# FLASH.net
KiCad netlist of a schematic drawn in Altium Designer
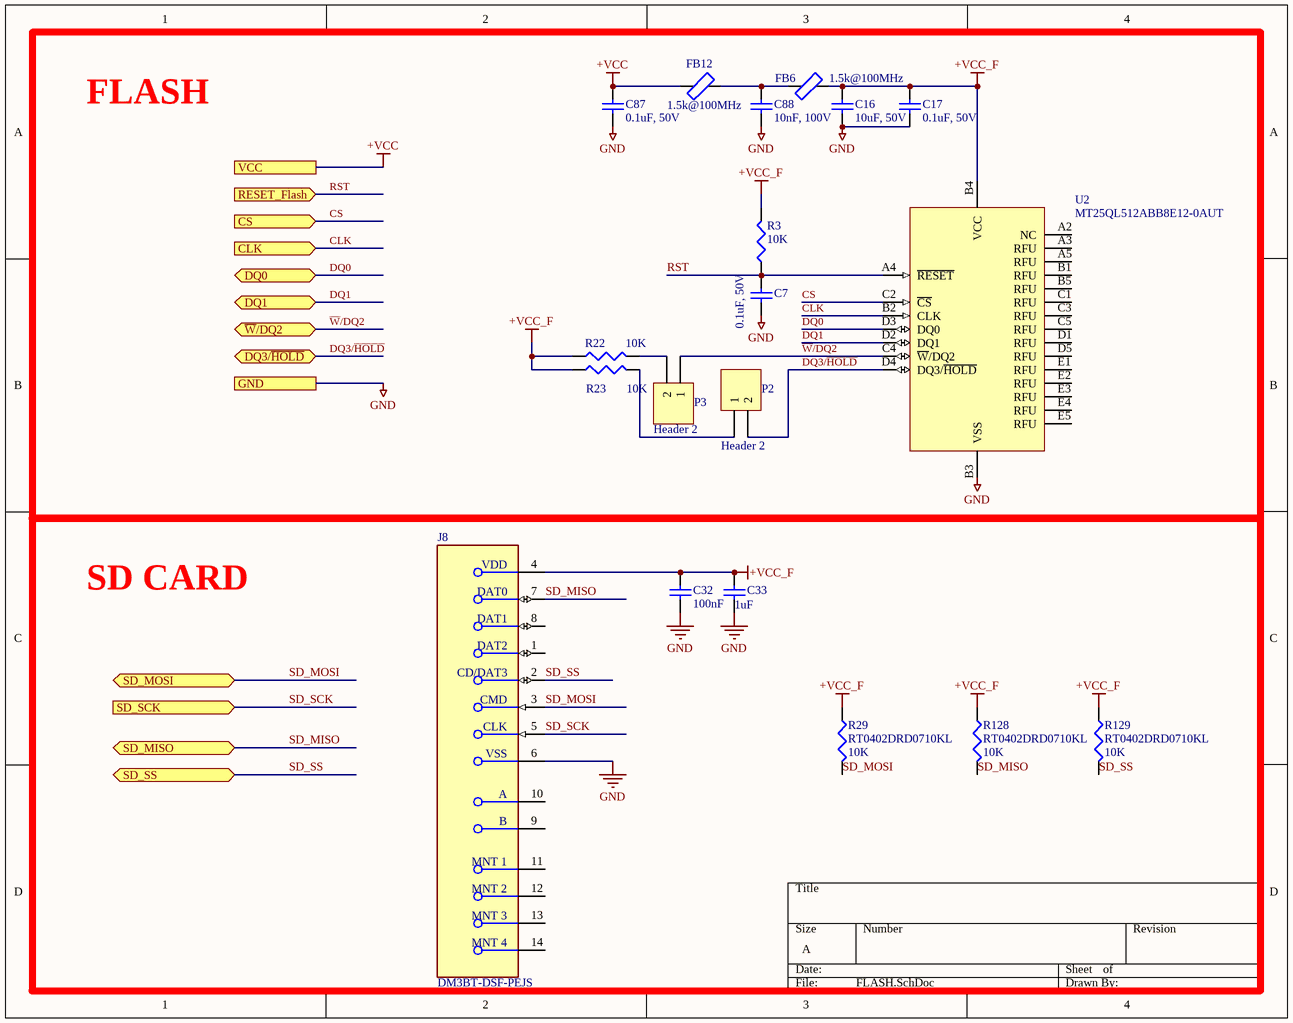
[diagram p0: FLASH.SchDoc]

(export (version "E")
  (design (tool "Eeschema 10.0.6"))
  (components
    (comp (ref "C7")
      (value "0.1uF, 50V")
      (footprint "0805")
      (description "0.10µF ±10% 50V Ceramic Capacitor X7R 0805 (2012 Metric)")
      (fields (field (name "PART NUMBER") "NS00353"))
      (libsource (lib "FullPartsDB") (part "Cap"))
    )
    (comp (ref "C16")
      (value "10uF, 50V")
      (footprint "1206")
      (description "CAP CER 10UF 50V X7R 1206")
      (fields (field (name "PART NUMBER") "NS00832"))
      (libsource (lib "FullPartsDB") (part "Cap"))
    )
    (comp (ref "C17")
      (value "0.1uF, 50V")
      (footprint "0805")
      (description "0.10µF ±10% 50V Ceramic Capacitor X7R 0805 (2012 Metric)")
      (fields (field (name "PART NUMBER") "NS00353"))
      (libsource (lib "FullPartsDB") (part "Cap"))
    )
    (comp (ref "C32")
      (value "100nF")
      (footprint "CAPC1005X55X30LL05T10")
      (libsource (lib "Altium Content Vault") (part "CAP"))
    )
    (comp (ref "C33")
      (value "1uF")
      (footprint "C1206")
      (description "Capacitor (Semiconductor SIM Model)")
      (fields (field (name "Comment") "C1206C105K4RACTU") (field (name "PUBLISHER") "Altium Limited"))
      (libsource (lib "Miscellaneous Devices") (part "Cap Semi"))
    )
    (comp (ref "C87")
      (value "0.1uF, 50V")
      (footprint "0805")
      (description "0.10µF ±10% 50V Ceramic Capacitor X7R 0805 (2012 Metric)")
      (fields (field (name "PART NUMBER") "NS00353"))
      (libsource (lib "FullPartsDB") (part "Cap"))
    )
    (comp (ref "C88")
      (value "10nF, 100V")
      (footprint "0603")
      (description "CAP CER 10000PF 100V C0G 0603")
      (fields (field (name "PART NUMBER") "NS00848"))
      (libsource (lib "FullPartsDB") (part "Cap"))
    )
    (comp (ref "FB6")
      (value "1.5k@100MHz")
      (footprint "0805")
      (description "WE-CBA SMT EMI SUPPRESSION FERRITE")
      (fields (field (name "PART NUMBER") "NS00881"))
      (libsource (lib "FullPartsDB") (part "Bead"))
    )
    (comp (ref "FB12")
      (value "1.5k@100MHz")
      (footprint "0805")
      (description "WE-CBA SMT EMI SUPPRESSION FERRITE")
      (fields (field (name "PART NUMBER") "NS00881"))
      (libsource (lib "FullPartsDB") (part "Bead"))
    )
    (comp (ref "J8")
      (value "DM3BT-DSF-PEJS")
      (footprint "FP-DM3BT-DSF-PEJS-MFG")
      (description "CONN MICRO SD CARD PUSH-PUSH R/A")
      (libsource (lib "Altium Content Vault") (part "93546ed2a3e5f67d674769dc1278528"))
    )
    (comp (ref "P2")
      (value "Header 2")
      (footprint "HDR1X2")
      (description "Header, 2-Pin")
      (fields (field (name "PUBLISHER") "Altium Limited"))
      (libsource (lib "") (part "Header 2_1"))
    )
    (comp (ref "P3")
      (value "Header 2")
      (footprint "HDR1X2")
      (description "Header, 2-Pin")
      (fields (field (name "PUBLISHER") "Altium Limited"))
      (libsource (lib "Miscellaneous Connectors") (part "Header 2"))
    )
    (comp (ref "R3")
      (value "10K")
      (footprint "0603")
      (description "Resistor")
      (fields (field (name "Comment") "RT0603DRD0710KL") (field (name "PUBLISHER") "Altium Limited"))
      (libsource (lib "Miscellaneous Devices") (part "Res3"))
    )
    (comp (ref "R22")
      (value "10K")
      (footprint "J1-0603")
      (description "Resistor")
      (fields (field (name "Comment") "RT0603DRD0710KL") (field (name "PUBLISHER") "Altium Limited"))
      (libsource (lib "Miscellaneous Devices") (part "Res3"))
    )
    (comp (ref "R23")
      (value "10K")
      (footprint "J1-0603")
      (description "Resistor")
      (fields (field (name "Comment") "RT0603DRD0710KL") (field (name "PUBLISHER") "Altium Limited"))
      (libsource (lib "Miscellaneous Devices") (part "Res3"))
    )
    (comp (ref "R29")
      (value "RT0402DRD0710KL")
      (footprint "0402")
      (description "Resistor")
      (fields (field (name "ALTIUM_VALUE") "10K") (field (name "PUBLISHER") "Altium Limited"))
      (libsource (lib "Miscellaneous Devices") (part "Res3"))
    )
    (comp (ref "R128")
      (value "RT0402DRD0710KL")
      (footprint "0402")
      (description "Resistor")
      (fields (field (name "ALTIUM_VALUE") "10K") (field (name "PUBLISHER") "Altium Limited"))
      (libsource (lib "Miscellaneous Devices") (part "Res3"))
    )
    (comp (ref "R129")
      (value "RT0402DRD0710KL")
      (footprint "0402")
      (description "Resistor")
      (fields (field (name "ALTIUM_VALUE") "10K") (field (name "PUBLISHER") "Altium Limited"))
      (libsource (lib "Miscellaneous Devices") (part "Res3"))
    )
    (comp (ref "U2")
      (value "MT25QL512ABB8E12-0AUT")
      (footprint "BGA24C100P5X5_600X800X120")
      (description "IC FLASH 512MBIT SPI 24TPBGA")
      (fields (field (name "PART NUMBER") "NS00922"))
      (libsource (lib "FullPartsDB") (part "MICRON_MT25QXXXXXXX8E12"))
    )
  )
  (nets
    (net (code "1") (name "+VCC") (class "Default")
      (node (ref "C87") (pin "2") (pinfunction "2_2") (pintype "passive"))
      (node (ref "FB12") (pin "2") (pinfunction "2_2") (pintype "passive"))
    )
    (net (code "2") (name "+VCC_F") (class "Default")
      (node (ref "C16") (pin "2") (pinfunction "2_2") (pintype "passive"))
      (node (ref "C17") (pin "2") (pinfunction "2_2") (pintype "passive"))
      (node (ref "C32") (pin "2") (pinfunction "2_2") (pintype "passive"))
      (node (ref "C33") (pin "2") (pinfunction "2_2") (pintype "passive"))
      (node (ref "FB6") (pin "2") (pinfunction "2_2") (pintype "passive"))
      (node (ref "J8") (pin "4") (pinfunction "VDD_4") (pintype "power_in"))
      (node (ref "R128") (pin "1") (pinfunction "1_1") (pintype "passive"))
      (node (ref "R129") (pin "1") (pinfunction "1_1") (pintype "passive"))
      (node (ref "R22") (pin "1") (pinfunction "1_1") (pintype "passive"))
      (node (ref "R23") (pin "1") (pinfunction "1_1") (pintype "passive"))
      (node (ref "R29") (pin "1") (pinfunction "1_1") (pintype "passive"))
      (node (ref "R3") (pin "2") (pinfunction "2_2") (pintype "passive"))
      (node (ref "U2") (pin "B4") (pinfunction "VCC_B4") (pintype "power_in"))
    )
    (net (code "3") (name "/CLK") (class "Default")
      (node (ref "U2") (pin "B2") (pinfunction "CLK_B2") (pintype "input"))
    )
    (net (code "4") (name "/CS") (class "Default")
      (node (ref "U2") (pin "C2") (pinfunction "CS_C2") (pintype "input"))
    )
    (net (code "5") (name "/DQ0") (class "Default")
      (node (ref "U2") (pin "D3") (pinfunction "DQ0_D3") (pintype "bidirectional"))
    )
    (net (code "6") (name "/DQ1") (class "Default")
      (node (ref "U2") (pin "D2") (pinfunction "DQ1_D2") (pintype "bidirectional"))
    )
    (net (code "7") (name "/DQ3{slash}~{HOLD}") (class "Default")
      (node (ref "P2") (pin "2") (pinfunction "2_2") (pintype "passive"))
      (node (ref "U2") (pin "D4") (pinfunction "DQ3/~{HOLD}_D4") (pintype "bidirectional"))
    )
    (net (code "8") (name "/RST") (class "Default")
      (node (ref "C7") (pin "2") (pinfunction "2_2") (pintype "passive"))
      (node (ref "R3") (pin "1") (pinfunction "1_1") (pintype "passive"))
      (node (ref "U2") (pin "A4") (pinfunction "RESET_A4") (pintype "input"))
    )
    (net (code "9") (name "/SD_MISO") (class "Default")
      (node (ref "J8") (pin "7") (pinfunction "DAT0_7") (pintype "bidirectional"))
      (node (ref "R128") (pin "2") (pinfunction "2_2") (pintype "passive"))
    )
    (net (code "10") (name "/SD_MOSI") (class "Default")
      (node (ref "J8") (pin "3") (pinfunction "CMD_3") (pintype "input"))
      (node (ref "R29") (pin "2") (pinfunction "2_2") (pintype "passive"))
    )
    (net (code "11") (name "/SD_SCK") (class "Default")
      (node (ref "J8") (pin "5") (pinfunction "CLK_5") (pintype "input"))
    )
    (net (code "12") (name "/SD_SS") (class "Default")
      (node (ref "J8") (pin "2") (pinfunction "CD/DAT3_2") (pintype "bidirectional"))
      (node (ref "R129") (pin "2") (pinfunction "2_2") (pintype "passive"))
    )
    (net (code "13") (name "/~{W}{slash}DQ2") (class "Default")
      (node (ref "P3") (pin "1") (pinfunction "1_1") (pintype "passive"))
      (node (ref "U2") (pin "C4") (pinfunction "~{W}/DQ2_C4") (pintype "bidirectional"))
    )
    (net (code "14") (name "GND") (class "Default")
      (node (ref "C16") (pin "1") (pinfunction "1_1") (pintype "passive"))
      (node (ref "C17") (pin "1") (pinfunction "1_1") (pintype "passive"))
      (node (ref "C32") (pin "1") (pinfunction "1_1") (pintype "passive"))
      (node (ref "C33") (pin "1") (pinfunction "1_1") (pintype "passive"))
      (node (ref "C7") (pin "1") (pinfunction "1_1") (pintype "passive"))
      (node (ref "C87") (pin "1") (pinfunction "1_1") (pintype "passive"))
      (node (ref "C88") (pin "2") (pinfunction "2_2") (pintype "passive"))
      (node (ref "J8") (pin "6") (pinfunction "VSS_6") (pintype "power_in"))
      (node (ref "U2") (pin "B3") (pinfunction "VSS_B3") (pintype "power_in"))
    )
    (net (code "15") (name "Net-(C88-Pad1)") (class "Default")
      (node (ref "C88") (pin "1") (pinfunction "1_1") (pintype "passive"))
      (node (ref "FB12") (pin "1") (pinfunction "1_1") (pintype "passive"))
      (node (ref "FB6") (pin "1") (pinfunction "1_1") (pintype "passive"))
    )
    (net (code "16") (name "Net-(P2-Pad1)") (class "Default")
      (node (ref "P2") (pin "1") (pinfunction "1_1") (pintype "passive"))
      (node (ref "R23") (pin "2") (pinfunction "2_2") (pintype "passive"))
    )
    (net (code "17") (name "Net-(P3-Pad2)") (class "Default")
      (node (ref "P3") (pin "2") (pinfunction "2_2") (pintype "passive"))
      (node (ref "R22") (pin "2") (pinfunction "2_2") (pintype "passive"))
    )
    (net (code "18") (name "unconnected-(J8-A-Pad10)") (class "Default")
      (node (ref "J8") (pin "10") (pinfunction "A_10") (pintype "passive"))
    )
    (net (code "19") (name "unconnected-(J8-B-Pad9)") (class "Default")
      (node (ref "J8") (pin "9") (pinfunction "B_9") (pintype "passive"))
    )
    (net (code "20") (name "unconnected-(J8-DAT1-Pad8)") (class "Default")
      (node (ref "J8") (pin "8") (pinfunction "DAT1_8") (pintype "bidirectional"))
    )
    (net (code "21") (name "unconnected-(J8-DAT2-Pad1)") (class "Default")
      (node (ref "J8") (pin "1") (pinfunction "DAT2_1") (pintype "bidirectional"))
    )
    (net (code "22") (name "unconnected-(J8-MNT_1-Pad11)") (class "Default")
      (node (ref "J8") (pin "11") (pinfunction "MNT_1_11") (pintype "passive"))
    )
    (net (code "23") (name "unconnected-(J8-MNT_2-Pad12)") (class "Default")
      (node (ref "J8") (pin "12") (pinfunction "MNT_2_12") (pintype "passive"))
    )
    (net (code "24") (name "unconnected-(J8-MNT_3-Pad13)") (class "Default")
      (node (ref "J8") (pin "13") (pinfunction "MNT_3_13") (pintype "passive"))
    )
    (net (code "25") (name "unconnected-(J8-MNT_4-Pad14)") (class "Default")
      (node (ref "J8") (pin "14") (pinfunction "MNT_4_14") (pintype "passive"))
    )
    (net (code "26") (name "unconnected-(U2-NC-PadA2)") (class "Default")
      (node (ref "U2") (pin "A2") (pinfunction "NC_A2") (pintype "passive"))
    )
    (net (code "27") (name "unconnected-(U2-RFU-PadA3)") (class "Default")
      (node (ref "U2") (pin "A3") (pinfunction "RFU_A3") (pintype "passive"))
    )
    (net (code "28") (name "unconnected-(U2-RFU-PadA5)") (class "Default")
      (node (ref "U2") (pin "A5") (pinfunction "RFU_A5") (pintype "passive"))
    )
    (net (code "29") (name "unconnected-(U2-RFU-PadB1)") (class "Default")
      (node (ref "U2") (pin "B1") (pinfunction "RFU_B1") (pintype "passive"))
    )
    (net (code "30") (name "unconnected-(U2-RFU-PadB5)") (class "Default")
      (node (ref "U2") (pin "B5") (pinfunction "RFU_B5") (pintype "passive"))
    )
    (net (code "31") (name "unconnected-(U2-RFU-PadC1)") (class "Default")
      (node (ref "U2") (pin "C1") (pinfunction "RFU_C1") (pintype "passive"))
    )
    (net (code "32") (name "unconnected-(U2-RFU-PadC3)") (class "Default")
      (node (ref "U2") (pin "C3") (pinfunction "RFU_C3") (pintype "passive"))
    )
    (net (code "33") (name "unconnected-(U2-RFU-PadC5)") (class "Default")
      (node (ref "U2") (pin "C5") (pinfunction "RFU_C5") (pintype "passive"))
    )
    (net (code "34") (name "unconnected-(U2-RFU-PadD1)") (class "Default")
      (node (ref "U2") (pin "D1") (pinfunction "RFU_D1") (pintype "passive"))
    )
    (net (code "35") (name "unconnected-(U2-RFU-PadD5)") (class "Default")
      (node (ref "U2") (pin "D5") (pinfunction "RFU_D5") (pintype "passive"))
    )
    (net (code "36") (name "unconnected-(U2-RFU-PadE1)") (class "Default")
      (node (ref "U2") (pin "E1") (pinfunction "RFU_E1") (pintype "passive"))
    )
    (net (code "37") (name "unconnected-(U2-RFU-PadE2)") (class "Default")
      (node (ref "U2") (pin "E2") (pinfunction "RFU_E2") (pintype "passive"))
    )
    (net (code "38") (name "unconnected-(U2-RFU-PadE3)") (class "Default")
      (node (ref "U2") (pin "E3") (pinfunction "RFU_E3") (pintype "passive"))
    )
    (net (code "39") (name "unconnected-(U2-RFU-PadE4)") (class "Default")
      (node (ref "U2") (pin "E4") (pinfunction "RFU_E4") (pintype "passive"))
    )
    (net (code "40") (name "unconnected-(U2-RFU-PadE5)") (class "Default")
      (node (ref "U2") (pin "E5") (pinfunction "RFU_E5") (pintype "passive"))
    )
  )
)
